# poe.net
KiCad netlist of a schematic drawn in EAGLE
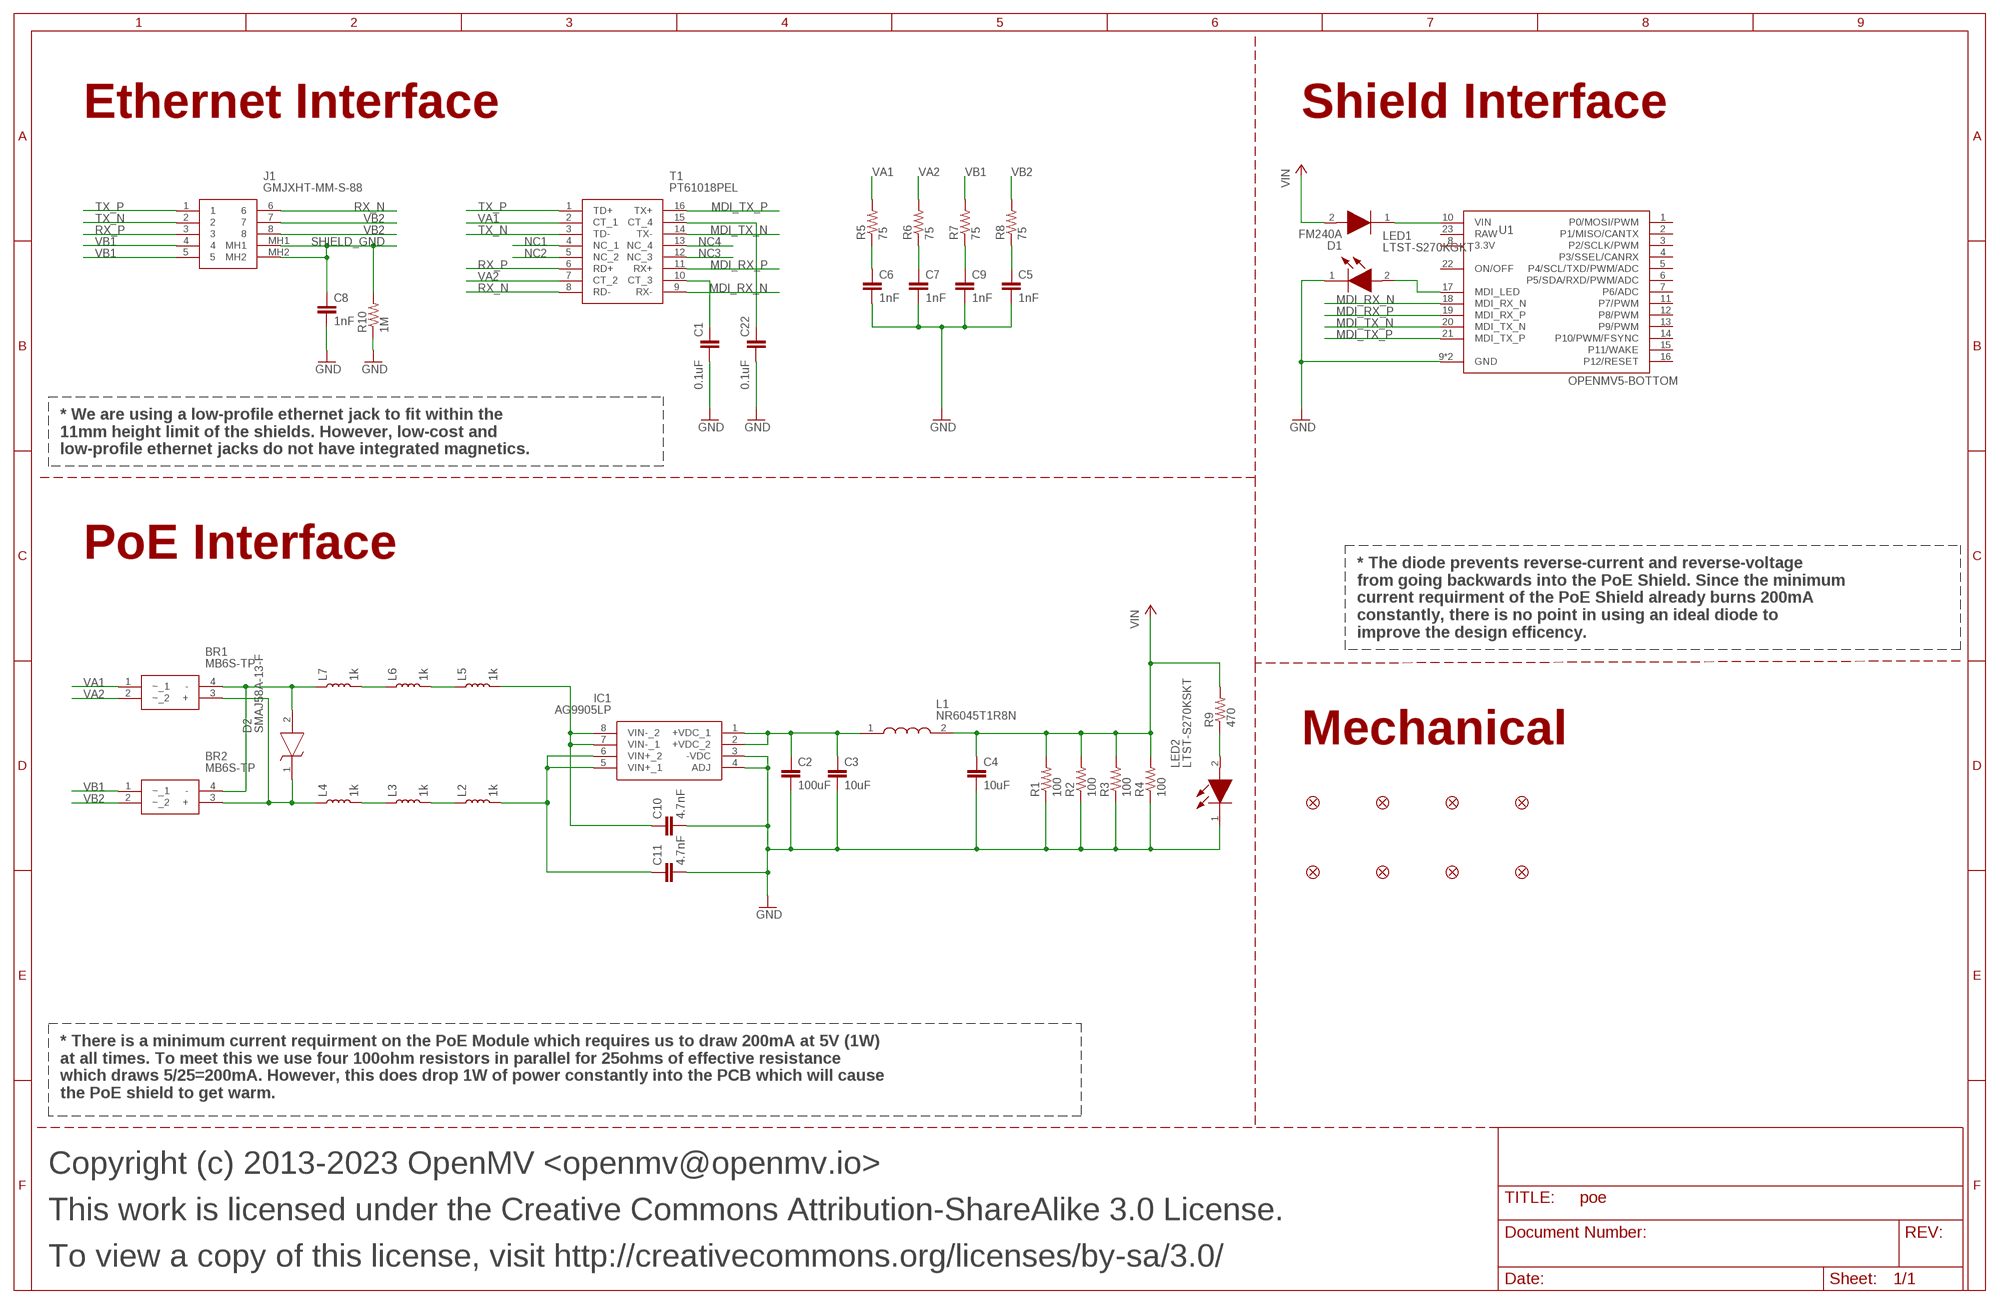
[diagram p0: schematic, sheet 1]

(export (version "E")
  (design (tool "Eeschema 10.0.6"))
  (components
    (comp (ref "BR1")
      (value "MB6S-TP")
      (footprint "eagle-import:SOP254P665X270-4N")
      (fields (field (name "MOUSER_PART_NUMBER") "833-MB6S-TP"))
      (libsource (lib "eagle-import") (part "MB6S-TP"))
    )
    (comp (ref "BR2")
      (value "MB6S-TP")
      (footprint "eagle-import:SOP254P665X270-4N")
      (fields (field (name "MOUSER_PART_NUMBER") "833-MB6S-TP"))
      (libsource (lib "eagle-import") (part "MB6S-TP"))
    )
    (comp (ref "C1")
      (value "0.1uF")
      (footprint "eagle-import:C0201")
      (fields (field (name "MPN") "CL03A104KQ3NNNC"))
      (libsource (lib "eagle-import") (part "C-EUC0201"))
    )
    (comp (ref "C2")
      (value "100uF")
      (footprint "eagle-import:C1206")
      (fields (field (name "MPN") "CL31A107MQHNNWE"))
      (libsource (lib "eagle-import") (part "C-EUC1206"))
    )
    (comp (ref "C3")
      (value "10uF")
      (footprint "eagle-import:C0402")
      (fields (field (name "MPN") "GRM155R60J106ME05D"))
      (libsource (lib "eagle-import") (part "C-EUC0402"))
    )
    (comp (ref "C4")
      (value "10uF")
      (footprint "eagle-import:C0402")
      (fields (field (name "MPN") "GRM155R60J106ME05D"))
      (libsource (lib "eagle-import") (part "C-EUC0402"))
    )
    (comp (ref "C5")
      (value "1nF")
      (footprint "eagle-import:C1206")
      (fields (field (name "MPN") "1206B102K252CT"))
      (libsource (lib "eagle-import") (part "C-EUC1206"))
    )
    (comp (ref "C6")
      (value "1nF")
      (footprint "eagle-import:C1206")
      (fields (field (name "MPN") "1206B102K252CT"))
      (libsource (lib "eagle-import") (part "C-EUC1206"))
    )
    (comp (ref "C7")
      (value "1nF")
      (footprint "eagle-import:C1206")
      (fields (field (name "MPN") "1206B102K252CT"))
      (libsource (lib "eagle-import") (part "C-EUC1206"))
    )
    (comp (ref "C8")
      (value "1nF")
      (footprint "eagle-import:C1206")
      (fields (field (name "MPN") "1206B102K252CT"))
      (libsource (lib "eagle-import") (part "C-EUC1206"))
    )
    (comp (ref "C9")
      (value "1nF")
      (footprint "eagle-import:C1206")
      (fields (field (name "MPN") "1206B102K252CT"))
      (libsource (lib "eagle-import") (part "C-EUC1206"))
    )
    (comp (ref "C10")
      (value "4.7nF")
      (footprint "eagle-import:C1812")
      (fields (field (name "MPN") "202S43W472KV4E"))
      (libsource (lib "eagle-import") (part "C-EUC1812"))
    )
    (comp (ref "C11")
      (value "4.7nF")
      (footprint "eagle-import:C1812")
      (fields (field (name "MPN") "202S43W472KV4E"))
      (libsource (lib "eagle-import") (part "C-EUC1812"))
    )
    (comp (ref "C22")
      (value "0.1uF")
      (footprint "eagle-import:C0201")
      (fields (field (name "MPN") "CL03A104KQ3NNNC"))
      (libsource (lib "eagle-import") (part "C-EUC0201"))
    )
    (comp (ref "D1")
      (value "FM240A")
      (footprint "eagle-import:DIOM5025X231N")
      (fields (field (name "MOUSER_PART_NUMBER") "583-FM240A"))
      (libsource (lib "eagle-import") (part "FM240A"))
    )
    (comp (ref "D2")
      (value "SMAJ58A-13-F")
      (footprint "eagle-import:DIOM5226X230N")
      (fields (field (name "MOUSER_PART_NUMBER") "621-SMAJ58A-13-F") (field (name "MPN") "SMAJ58A/TR13"))
      (libsource (lib "eagle-import") (part "SMAJ58A-13-F"))
    )
    (comp (ref "FD1")
      (value "FIDUCIAL1X2")
      (footprint "eagle-import:FIDUCIAL-1X2")
      (libsource (lib "eagle-import") (part "FIDUCIAL1X2"))
    )
    (comp (ref "FD2")
      (value "FIDUCIAL1X2")
      (footprint "eagle-import:FIDUCIAL-1X2")
      (libsource (lib "eagle-import") (part "FIDUCIAL1X2"))
    )
    (comp (ref "FD3")
      (value "FIDUCIAL1X2")
      (footprint "eagle-import:FIDUCIAL-1X2")
      (libsource (lib "eagle-import") (part "FIDUCIAL1X2"))
    )
    (comp (ref "FD4")
      (value "FIDUCIAL1X2")
      (footprint "eagle-import:FIDUCIAL-1X2")
      (libsource (lib "eagle-import") (part "FIDUCIAL1X2"))
    )
    (comp (ref "FD5")
      (value "FIDUCIAL1X2")
      (footprint "eagle-import:FIDUCIAL-1X2")
      (libsource (lib "eagle-import") (part "FIDUCIAL1X2"))
    )
    (comp (ref "FD6")
      (value "FIDUCIAL1X2")
      (footprint "eagle-import:FIDUCIAL-1X2")
      (libsource (lib "eagle-import") (part "FIDUCIAL1X2"))
    )
    (comp (ref "FD7")
      (value "FIDUCIAL1X2")
      (footprint "eagle-import:FIDUCIAL-1X2")
      (libsource (lib "eagle-import") (part "FIDUCIAL1X2"))
    )
    (comp (ref "FD8")
      (value "FIDUCIAL1X2")
      (footprint "eagle-import:FIDUCIAL-1X2")
      (libsource (lib "eagle-import") (part "FIDUCIAL1X2"))
    )
    (comp (ref "IC1")
      (value "AG9905LP")
      (footprint "eagle-import:AG9905LP")
      (fields
        (field (name "MANUFACTURER_PART_NUMBER") "Ag9905LP")
        (field (name "MOUSER_PART_NUMBER") "480-AG9905LP")
      )
      (libsource (lib "eagle-import") (part "AG9905LP"))
    )
    (comp (ref "J1")
      (value "GMJXHT-MM-S-88")
      (footprint "eagle-import:GMJXHTMMS88")
      (fields (field (name "MOUSER_PART_NUMBER") "806-GMJXHT-MM-S-88"))
      (libsource (lib "eagle-import") (part "GMJXHT-MM-S-88"))
    )
    (comp (ref "L1")
      (value "NR6045T1R8N")
      (footprint "eagle-import:NR6045T1R8N")
      (fields (field (name "MOUSER_PART_NUMBER") "963-NR6045T1R8N"))
      (libsource (lib "eagle-import") (part "NR6045T1R8N"))
    )
    (comp (ref "L2")
      (value "1k")
      (footprint "eagle-import:0402")
      (fields (field (name "MPN") "BBPY00100505102Y00"))
      (libsource (lib "eagle-import") (part "INDUCTOR-0402-3.9NH"))
    )
    (comp (ref "L3")
      (value "1k")
      (footprint "eagle-import:0402")
      (fields (field (name "MPN") "BBPY00100505102Y00"))
      (libsource (lib "eagle-import") (part "INDUCTOR-0402-3.9NH"))
    )
    (comp (ref "L4")
      (value "1k")
      (footprint "eagle-import:0402")
      (fields (field (name "MPN") "BBPY00100505102Y00"))
      (libsource (lib "eagle-import") (part "INDUCTOR-0402-3.9NH"))
    )
    (comp (ref "L5")
      (value "1k")
      (footprint "eagle-import:0402")
      (fields (field (name "MPN") "BBPY00100505102Y00"))
      (libsource (lib "eagle-import") (part "INDUCTOR-0402-3.9NH"))
    )
    (comp (ref "L6")
      (value "1k")
      (footprint "eagle-import:0402")
      (fields (field (name "MPN") "BBPY00100505102Y00"))
      (libsource (lib "eagle-import") (part "INDUCTOR-0402-3.9NH"))
    )
    (comp (ref "L7")
      (value "1k")
      (footprint "eagle-import:0402")
      (fields (field (name "MPN") "BBPY00100505102Y00"))
      (libsource (lib "eagle-import") (part "INDUCTOR-0402-3.9NH"))
    )
    (comp (ref "LED1")
      (value "LTST-S270KGKT")
      (footprint "eagle-import:LTSTS270K")
      (fields (field (name "MOUSER_PART_NUMBER") "859-LTST-S270KGKT"))
      (libsource (lib "eagle-import") (part "LTST-S270KGKT"))
    )
    (comp (ref "LED2")
      (value "LTST-S270KSKT")
      (footprint "eagle-import:LTSTS270K")
      (fields (field (name "MOUSER_PART_NUMBER") "859-LTST-S270KSKT"))
      (libsource (lib "eagle-import") (part "LTST-S270KSKT"))
    )
    (comp (ref "R1")
      (value "100")
      (footprint "eagle-import:R2512")
      (fields (field (name "MPN") "RC2512JK-07100RL"))
      (libsource (lib "eagle-import") (part "R-US_R2512"))
    )
    (comp (ref "R2")
      (value "100")
      (footprint "eagle-import:R2512")
      (fields (field (name "MPN") "RC2512JK-07100RL"))
      (libsource (lib "eagle-import") (part "R-US_R2512"))
    )
    (comp (ref "R3")
      (value "100")
      (footprint "eagle-import:R2512")
      (fields (field (name "MPN") "RC2512JK-07100RL"))
      (libsource (lib "eagle-import") (part "R-US_R2512"))
    )
    (comp (ref "R4")
      (value "100")
      (footprint "eagle-import:R2512")
      (fields (field (name "MPN") "RC2512JK-07100RL"))
      (libsource (lib "eagle-import") (part "R-US_R2512"))
    )
    (comp (ref "R5")
      (value "75")
      (footprint "eagle-import:R0402")
      (fields (field (name "MPN") "0402WGF750JTCE"))
      (libsource (lib "eagle-import") (part "R-US_R0402"))
    )
    (comp (ref "R6")
      (value "75")
      (footprint "eagle-import:R0402")
      (fields (field (name "MPN") "0402WGF750JTCE"))
      (libsource (lib "eagle-import") (part "R-US_R0402"))
    )
    (comp (ref "R7")
      (value "75")
      (footprint "eagle-import:R0402")
      (fields (field (name "MPN") "0402WGF750JTCE"))
      (libsource (lib "eagle-import") (part "R-US_R0402"))
    )
    (comp (ref "R8")
      (value "75")
      (footprint "eagle-import:R0402")
      (fields (field (name "MPN") "0402WGF750JTCE"))
      (libsource (lib "eagle-import") (part "R-US_R0402"))
    )
    (comp (ref "R9")
      (value "470")
      (footprint "eagle-import:R0603")
      (fields (field (name "MPN") "0603WAJ0471T5E"))
      (libsource (lib "eagle-import") (part "R-US_R0603"))
    )
    (comp (ref "R10")
      (value "1M")
      (footprint "eagle-import:R1206")
      (fields (field (name "MPN") "RMCF1206FT1M00"))
      (libsource (lib "eagle-import") (part "R-US_R1206"))
    )
    (comp (ref "T1")
      (value "PT61018PEL")
      (footprint "eagle-import:SOIC127P930X565-16N")
      (fields (field (name "MOUSER_PART_NUMBER") "652-PT61018PEL"))
      (libsource (lib "eagle-import") (part "PT61018PEL"))
    )
    (comp (ref "U1")
      (value "OPENMV5-BOTTOM")
      (footprint "eagle-import:OPENMV5-BOTTOM")
      (libsource (lib "eagle-import") (part "OPENMV5-BOTTOM"))
    )
  )
  (nets
    (net (code "1") (name "/3.3V") (class "Default")
      (node (ref "U1") (pin "8") (pinfunction "3.3V_8") (pintype "power_in"))
    )
    (net (code "2") (name "/MDI_RX_N") (class "Default")
      (node (ref "T1") (pin "9") (pinfunction "RX-_9") (pintype "bidirectional"))
      (node (ref "U1") (pin "18") (pinfunction "MDI_RX_N_18") (pintype "bidirectional"))
    )
    (net (code "3") (name "/MDI_RX_P") (class "Default")
      (node (ref "T1") (pin "11") (pinfunction "RX+_11") (pintype "bidirectional"))
      (node (ref "U1") (pin "19") (pinfunction "MDI_RX_P_19") (pintype "bidirectional"))
    )
    (net (code "4") (name "/MDI_TX_N") (class "Default")
      (node (ref "T1") (pin "14") (pinfunction "TX-_14") (pintype "bidirectional"))
      (node (ref "U1") (pin "20") (pinfunction "MDI_TX_N_20") (pintype "bidirectional"))
    )
    (net (code "5") (name "/MDI_TX_P") (class "Default")
      (node (ref "T1") (pin "16") (pinfunction "TX+_16") (pintype "bidirectional"))
      (node (ref "U1") (pin "21") (pinfunction "MDI_TX_P_21") (pintype "bidirectional"))
    )
    (net (code "6") (name "/NC1") (class "Default")
      (node (ref "T1") (pin "4") (pinfunction "NC_1_4") (pintype "bidirectional"))
    )
    (net (code "7") (name "/NC2") (class "Default")
      (node (ref "T1") (pin "5") (pinfunction "NC_2_5") (pintype "bidirectional"))
    )
    (net (code "8") (name "/NC3") (class "Default")
      (node (ref "T1") (pin "12") (pinfunction "NC_3_12") (pintype "bidirectional"))
    )
    (net (code "9") (name "/NC4") (class "Default")
      (node (ref "T1") (pin "13") (pinfunction "NC_4_13") (pintype "bidirectional"))
    )
    (net (code "10") (name "/RAW") (class "Default")
      (node (ref "U1") (pin "23") (pinfunction "RAW_23") (pintype "power_in"))
    )
    (net (code "11") (name "/RX_N") (class "Default")
      (node (ref "J1") (pin "6") (pinfunction "6_6") (pintype "bidirectional"))
      (node (ref "T1") (pin "8") (pinfunction "RD-_8") (pintype "bidirectional"))
    )
    (net (code "12") (name "/RX_P") (class "Default")
      (node (ref "J1") (pin "3") (pinfunction "3_3") (pintype "bidirectional"))
      (node (ref "T1") (pin "6") (pinfunction "RD+_6") (pintype "bidirectional"))
    )
    (net (code "13") (name "/SHIELD_GND") (class "Default")
      (node (ref "C8") (pin "1") (pinfunction "1_1") (pintype "passive"))
      (node (ref "J1") (pin "MH1") (pinfunction "MH1_MH1") (pintype "bidirectional"))
      (node (ref "J1") (pin "MH2") (pinfunction "MH2_MH2") (pintype "bidirectional"))
      (node (ref "R10") (pin "2") (pinfunction "2_2") (pintype "passive"))
    )
    (net (code "14") (name "/TX_N") (class "Default")
      (node (ref "J1") (pin "2") (pinfunction "2_2") (pintype "bidirectional"))
      (node (ref "T1") (pin "3") (pinfunction "TD-_3") (pintype "bidirectional"))
    )
    (net (code "15") (name "/TX_P") (class "Default")
      (node (ref "J1") (pin "1") (pinfunction "1_1") (pintype "bidirectional"))
      (node (ref "T1") (pin "1") (pinfunction "TD+_1") (pintype "bidirectional"))
    )
    (net (code "16") (name "/VA1") (class "Default")
      (node (ref "BR1") (pin "1") (pinfunction "~{_1}_1") (pintype "bidirectional"))
      (node (ref "R5") (pin "2") (pinfunction "2_2") (pintype "passive"))
      (node (ref "T1") (pin "2") (pinfunction "CT_1_2") (pintype "bidirectional"))
    )
    (net (code "17") (name "/VA2") (class "Default")
      (node (ref "BR1") (pin "2") (pinfunction "~{_2}_2") (pintype "bidirectional"))
      (node (ref "R6") (pin "2") (pinfunction "2_2") (pintype "passive"))
      (node (ref "T1") (pin "7") (pinfunction "CT_2_7") (pintype "bidirectional"))
    )
    (net (code "18") (name "/VB1") (class "Default")
      (node (ref "BR2") (pin "1") (pinfunction "~{_1}_1") (pintype "bidirectional"))
      (node (ref "J1") (pin "4") (pinfunction "4_4") (pintype "bidirectional"))
      (node (ref "J1") (pin "5") (pinfunction "5_5") (pintype "bidirectional"))
      (node (ref "R7") (pin "2") (pinfunction "2_2") (pintype "passive"))
    )
    (net (code "19") (name "/VB2") (class "Default")
      (node (ref "BR2") (pin "2") (pinfunction "~{_2}_2") (pintype "bidirectional"))
      (node (ref "J1") (pin "7") (pinfunction "7_7") (pintype "bidirectional"))
      (node (ref "J1") (pin "8") (pinfunction "8_8") (pintype "bidirectional"))
      (node (ref "R8") (pin "2") (pinfunction "2_2") (pintype "passive"))
    )
    (net (code "20") (name "GND") (class "Default")
      (node (ref "C1") (pin "2") (pinfunction "2_2") (pintype "passive"))
      (node (ref "C10") (pin "2") (pinfunction "2_2") (pintype "passive"))
      (node (ref "C11") (pin "2") (pinfunction "2_2") (pintype "passive"))
      (node (ref "C2") (pin "2") (pinfunction "2_2") (pintype "passive"))
      (node (ref "C22") (pin "2") (pinfunction "2_2") (pintype "passive"))
      (node (ref "C3") (pin "2") (pinfunction "2_2") (pintype "passive"))
      (node (ref "C4") (pin "2") (pinfunction "2_2") (pintype "passive"))
      (node (ref "C5") (pin "2") (pinfunction "2_2") (pintype "passive"))
      (node (ref "C6") (pin "2") (pinfunction "2_2") (pintype "passive"))
      (node (ref "C7") (pin "2") (pinfunction "2_2") (pintype "passive"))
      (node (ref "C8") (pin "2") (pinfunction "2_2") (pintype "passive"))
      (node (ref "C9") (pin "2") (pinfunction "2_2") (pintype "passive"))
      (node (ref "IC1") (pin "3") (pinfunction "-VDC_3") (pintype "bidirectional"))
      (node (ref "IC1") (pin "4") (pinfunction "ADJ_4") (pintype "bidirectional"))
      (node (ref "LED1") (pin "1") (pinfunction "K_1") (pintype "bidirectional"))
      (node (ref "LED2") (pin "1") (pinfunction "K_1") (pintype "bidirectional"))
      (node (ref "R1") (pin "1") (pinfunction "1_1") (pintype "passive"))
      (node (ref "R10") (pin "1") (pinfunction "1_1") (pintype "passive"))
      (node (ref "R2") (pin "1") (pinfunction "1_1") (pintype "passive"))
      (node (ref "R3") (pin "1") (pinfunction "1_1") (pintype "passive"))
      (node (ref "R4") (pin "1") (pinfunction "1_1") (pintype "passive"))
      (node (ref "U1") (pin "24") (pinfunction "GND_24") (pintype "power_in"))
      (node (ref "U1") (pin "9") (pinfunction "GND_9") (pintype "power_in"))
    )
    (net (code "21") (name "Net-(BR1-+)") (class "Default")
      (node (ref "BR1") (pin "3") (pinfunction "+_3") (pintype "bidirectional"))
      (node (ref "BR2") (pin "3") (pinfunction "+_3") (pintype "bidirectional"))
      (node (ref "D2") (pin "1") (pinfunction "K_1") (pintype "bidirectional"))
      (node (ref "L4") (pin "1") (pinfunction "1_1") (pintype "passive"))
    )
    (net (code "22") (name "Net-(BR1--)") (class "Default")
      (node (ref "BR1") (pin "4") (pinfunction "-_4") (pintype "bidirectional"))
      (node (ref "BR2") (pin "4") (pinfunction "-_4") (pintype "bidirectional"))
      (node (ref "D2") (pin "2") (pinfunction "A_2") (pintype "bidirectional"))
      (node (ref "L7") (pin "1") (pinfunction "1_1") (pintype "passive"))
    )
    (net (code "23") (name "Net-(C5-Pad1)") (class "Default")
      (node (ref "C5") (pin "1") (pinfunction "1_1") (pintype "passive"))
      (node (ref "R8") (pin "1") (pinfunction "1_1") (pintype "passive"))
    )
    (net (code "24") (name "Net-(C6-Pad1)") (class "Default")
      (node (ref "C6") (pin "1") (pinfunction "1_1") (pintype "passive"))
      (node (ref "R5") (pin "1") (pinfunction "1_1") (pintype "passive"))
    )
    (net (code "25") (name "Net-(C7-Pad1)") (class "Default")
      (node (ref "C7") (pin "1") (pinfunction "1_1") (pintype "passive"))
      (node (ref "R6") (pin "1") (pinfunction "1_1") (pintype "passive"))
    )
    (net (code "26") (name "Net-(C9-Pad1)") (class "Default")
      (node (ref "C9") (pin "1") (pinfunction "1_1") (pintype "passive"))
      (node (ref "R7") (pin "1") (pinfunction "1_1") (pintype "passive"))
    )
    (net (code "27") (name "Net-(D1-K)") (class "Default")
      (node (ref "D1") (pin "1") (pinfunction "K_1") (pintype "bidirectional"))
      (node (ref "U1") (pin "10") (pinfunction "VIN_10") (pintype "power_in"))
    )
    (net (code "28") (name "Net-(IC1-+VDC_1)") (class "Default")
      (node (ref "C2") (pin "1") (pinfunction "1_1") (pintype "passive"))
      (node (ref "C3") (pin "1") (pinfunction "1_1") (pintype "passive"))
      (node (ref "IC1") (pin "1") (pinfunction "+VDC_1_1") (pintype "bidirectional"))
      (node (ref "IC1") (pin "2") (pinfunction "+VDC_2_2") (pintype "bidirectional"))
      (node (ref "L1") (pin "1") (pinfunction "1_1") (pintype "bidirectional"))
    )
    (net (code "29") (name "Net-(IC1-VIN+_1)") (class "Default")
      (node (ref "C11") (pin "1") (pinfunction "1_1") (pintype "passive"))
      (node (ref "IC1") (pin "5") (pinfunction "VIN+_1_5") (pintype "bidirectional"))
      (node (ref "IC1") (pin "6") (pinfunction "VIN+_2_6") (pintype "bidirectional"))
      (node (ref "L2") (pin "2") (pinfunction "2_2") (pintype "passive"))
    )
    (net (code "30") (name "Net-(IC1-VIN-_1)") (class "Default")
      (node (ref "C10") (pin "1") (pinfunction "1_1") (pintype "passive"))
      (node (ref "IC1") (pin "7") (pinfunction "VIN-_1_7") (pintype "bidirectional"))
      (node (ref "IC1") (pin "8") (pinfunction "VIN-_2_8") (pintype "bidirectional"))
      (node (ref "L5") (pin "2") (pinfunction "2_2") (pintype "passive"))
    )
    (net (code "31") (name "Net-(L2-Pad1)") (class "Default")
      (node (ref "L2") (pin "1") (pinfunction "1_1") (pintype "passive"))
      (node (ref "L3") (pin "2") (pinfunction "2_2") (pintype "passive"))
    )
    (net (code "32") (name "Net-(L3-Pad1)") (class "Default")
      (node (ref "L3") (pin "1") (pinfunction "1_1") (pintype "passive"))
      (node (ref "L4") (pin "2") (pinfunction "2_2") (pintype "passive"))
    )
    (net (code "33") (name "Net-(L5-Pad1)") (class "Default")
      (node (ref "L5") (pin "1") (pinfunction "1_1") (pintype "passive"))
      (node (ref "L6") (pin "2") (pinfunction "2_2") (pintype "passive"))
    )
    (net (code "34") (name "Net-(L6-Pad1)") (class "Default")
      (node (ref "L6") (pin "1") (pinfunction "1_1") (pintype "passive"))
      (node (ref "L7") (pin "2") (pinfunction "2_2") (pintype "passive"))
    )
    (net (code "35") (name "Net-(LED1-A)") (class "Default")
      (node (ref "LED1") (pin "2") (pinfunction "A_2") (pintype "bidirectional"))
      (node (ref "U1") (pin "17") (pinfunction "MDI_LED_17") (pintype "bidirectional"))
    )
    (net (code "36") (name "Net-(LED2-A)") (class "Default")
      (node (ref "LED2") (pin "2") (pinfunction "A_2") (pintype "bidirectional"))
      (node (ref "R9") (pin "1") (pinfunction "1_1") (pintype "passive"))
    )
    (net (code "37") (name "Net-(T1-CT_3)") (class "Default")
      (node (ref "C1") (pin "1") (pinfunction "1_1") (pintype "passive"))
      (node (ref "T1") (pin "10") (pinfunction "CT_3_10") (pintype "bidirectional"))
    )
    (net (code "38") (name "Net-(T1-CT_4)") (class "Default")
      (node (ref "C22") (pin "1") (pinfunction "1_1") (pintype "passive"))
      (node (ref "T1") (pin "15") (pinfunction "CT_4_15") (pintype "bidirectional"))
    )
    (net (code "39") (name "VIN") (class "Default")
      (node (ref "C4") (pin "1") (pinfunction "1_1") (pintype "passive"))
      (node (ref "D1") (pin "2") (pinfunction "A_2") (pintype "bidirectional"))
      (node (ref "L1") (pin "2") (pinfunction "2_2") (pintype "bidirectional"))
      (node (ref "R1") (pin "2") (pinfunction "2_2") (pintype "passive"))
      (node (ref "R2") (pin "2") (pinfunction "2_2") (pintype "passive"))
      (node (ref "R3") (pin "2") (pinfunction "2_2") (pintype "passive"))
      (node (ref "R4") (pin "2") (pinfunction "2_2") (pintype "passive"))
      (node (ref "R9") (pin "2") (pinfunction "2_2") (pintype "passive"))
    )
    (net (code "40") (name "unconnected-(U1-ON{slash}OFF-Pad22)") (class "Default")
      (node (ref "U1") (pin "22") (pinfunction "ON/OFF_22") (pintype "bidirectional"))
    )
    (net (code "41") (name "unconnected-(U1-P0{slash}MOSI{slash}PWM-Pad1)") (class "Default")
      (node (ref "U1") (pin "1") (pinfunction "P0/MOSI/PWM_1") (pintype "bidirectional"))
    )
    (net (code "42") (name "unconnected-(U1-P1{slash}MISO{slash}CANTX-Pad2)") (class "Default")
      (node (ref "U1") (pin "2") (pinfunction "P1/MISO/CANTX_2") (pintype "bidirectional"))
    )
    (net (code "43") (name "unconnected-(U1-P2{slash}SCLK{slash}PWM-Pad3)") (class "Default")
      (node (ref "U1") (pin "3") (pinfunction "P2/SCLK/PWM_3") (pintype "bidirectional"))
    )
    (net (code "44") (name "unconnected-(U1-P3{slash}SSEL{slash}CANRX-Pad4)") (class "Default")
      (node (ref "U1") (pin "4") (pinfunction "P3/SSEL/CANRX_4") (pintype "bidirectional"))
    )
    (net (code "45") (name "unconnected-(U1-P4{slash}SCL{slash}TXD{slash}PWM{slash}ADC-Pad5)") (class "Default")
      (node (ref "U1") (pin "5") (pinfunction "P4/SCL/TXD/PWM/ADC_5") (pintype "bidirectional"))
    )
    (net (code "46") (name "unconnected-(U1-P5{slash}SDA{slash}RXD{slash}PWM{slash}ADC-Pad6)") (class "Default")
      (node (ref "U1") (pin "6") (pinfunction "P5/SDA/RXD/PWM/ADC_6") (pintype "bidirectional"))
    )
    (net (code "47") (name "unconnected-(U1-P6{slash}ADC-Pad7)") (class "Default")
      (node (ref "U1") (pin "7") (pinfunction "P6/ADC_7") (pintype "bidirectional"))
    )
    (net (code "48") (name "unconnected-(U1-P7{slash}PWM-Pad11)") (class "Default")
      (node (ref "U1") (pin "11") (pinfunction "P7/PWM_11") (pintype "bidirectional"))
    )
    (net (code "49") (name "unconnected-(U1-P8{slash}PWM-Pad12)") (class "Default")
      (node (ref "U1") (pin "12") (pinfunction "P8/PWM_12") (pintype "bidirectional"))
    )
    (net (code "50") (name "unconnected-(U1-P9{slash}PWM-Pad13)") (class "Default")
      (node (ref "U1") (pin "13") (pinfunction "P9/PWM_13") (pintype "bidirectional"))
    )
    (net (code "51") (name "unconnected-(U1-P10{slash}PWM{slash}FSYNC-Pad14)") (class "Default")
      (node (ref "U1") (pin "14") (pinfunction "P10/PWM/FSYNC_14") (pintype "bidirectional"))
    )
    (net (code "52") (name "unconnected-(U1-P11{slash}WAKE-Pad15)") (class "Default")
      (node (ref "U1") (pin "15") (pinfunction "P11/WAKE_15") (pintype "bidirectional"))
    )
    (net (code "53") (name "unconnected-(U1-P12{slash}RESET-Pad16)") (class "Default")
      (node (ref "U1") (pin "16") (pinfunction "P12/RESET_16") (pintype "bidirectional"))
    )
  )
)
